# ChargeModule.net
KiCad netlist of a schematic drawn in EAGLE
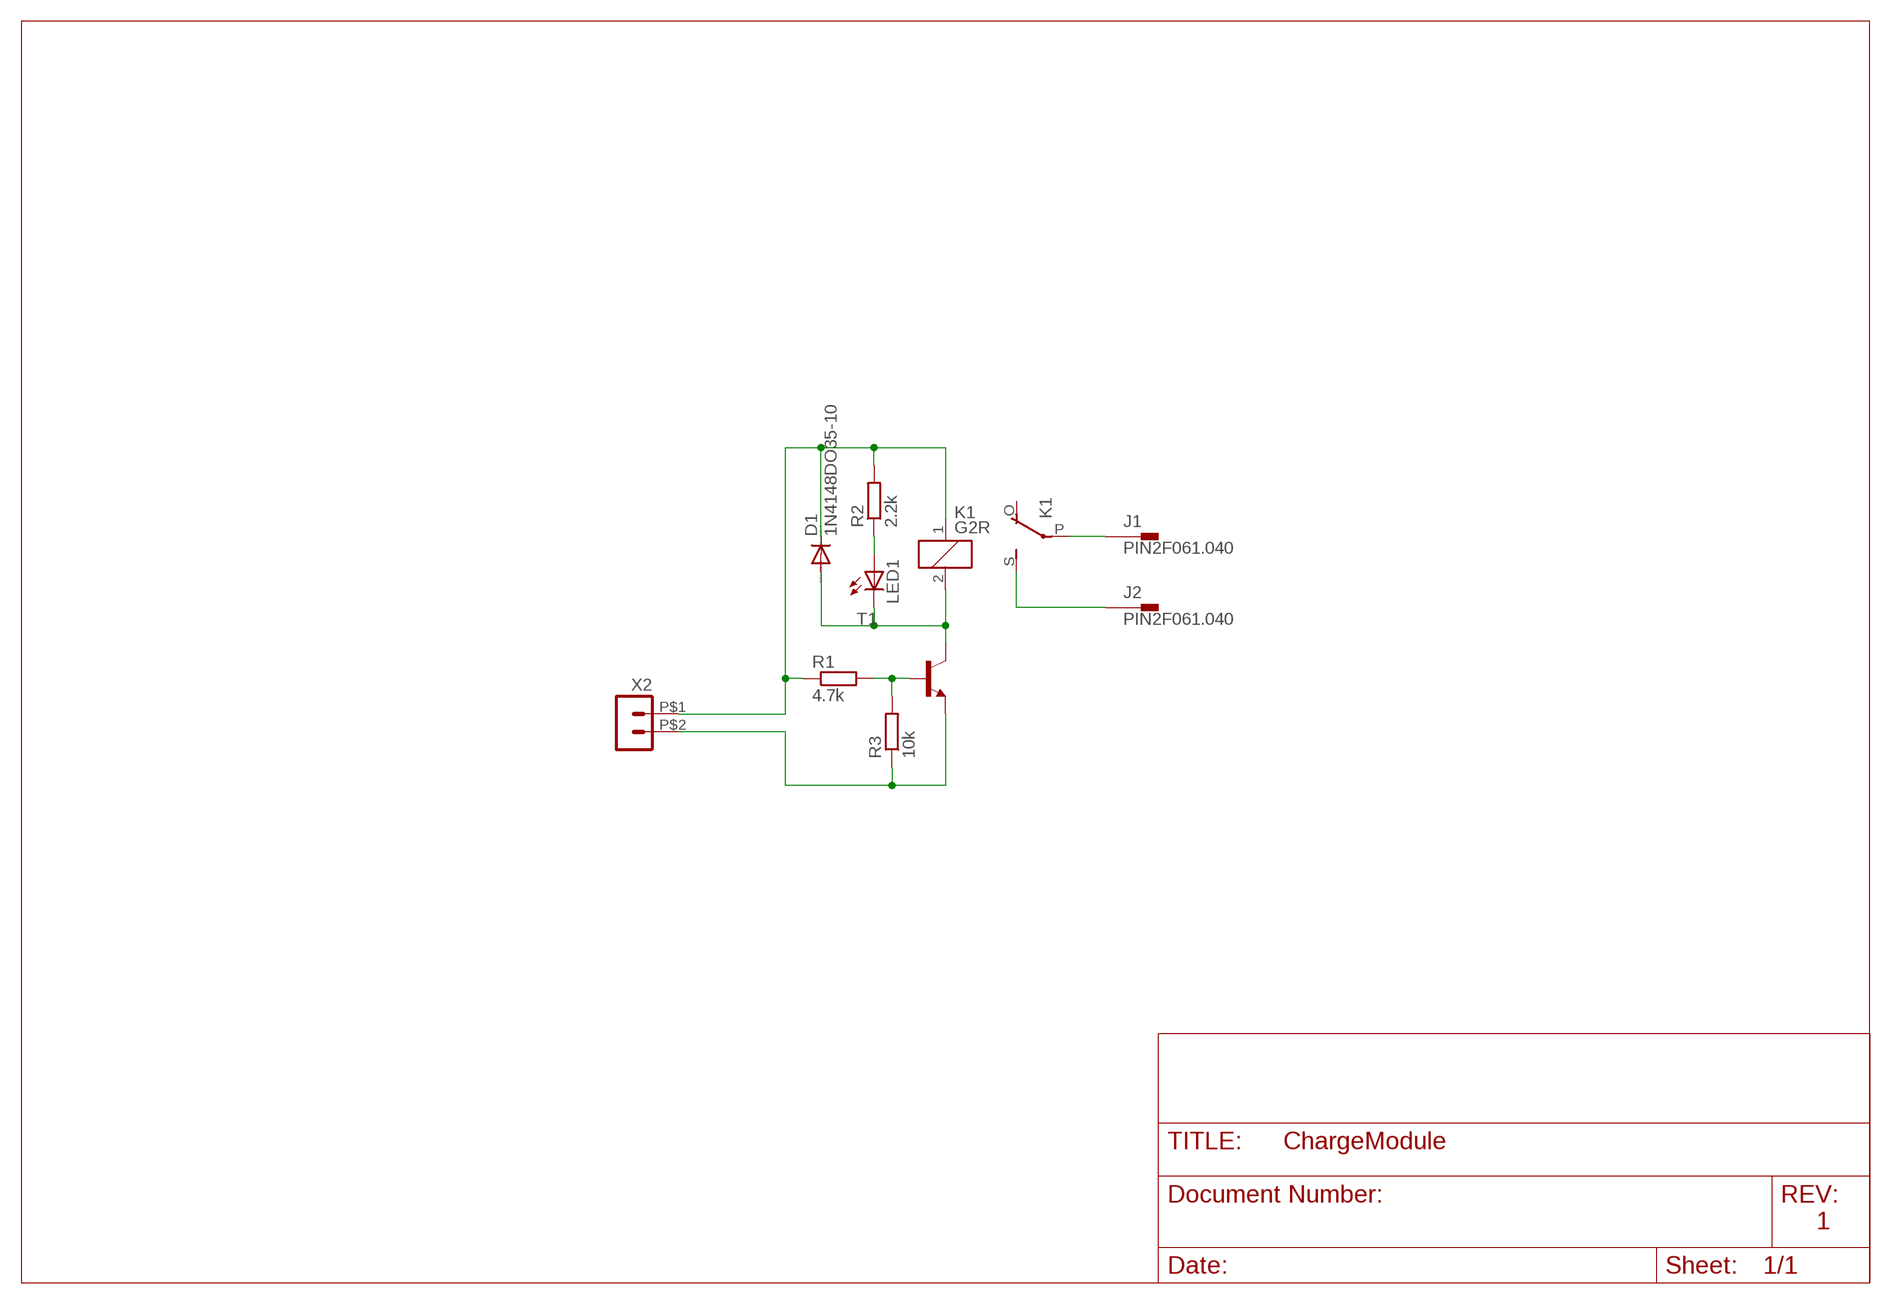
[diagram p0: schematic, sheet 1]

(export (version "E")
  (design (tool "Eeschema 10.0.6"))
  (components
    (comp (ref "D1")
      (value "1N4148DO35-10")
      (footprint "eagle-import:DO35-10")
      (libsource (lib "eagle-import") (part "1N4148DO35-10"))
    )
    (comp (ref "J1")
      (value "PIN2F061.040")
      (footprint "eagle-import:F061.040")
      (libsource (lib "eagle-import") (part "PIN2F061.040"))
    )
    (comp (ref "J2")
      (value "PIN2F061.040")
      (footprint "eagle-import:F061.040")
      (libsource (lib "eagle-import") (part "PIN2F061.040"))
    )
    (comp (ref "K1")
      (value "G2R")
      (footprint "eagle-import:G2R")
      (libsource (lib "eagle-import") (part "G2R"))
    )
    (comp (ref "LED1")
      (value "LED3MM")
      (footprint "eagle-import:LED3MM")
      (libsource (lib "eagle-import") (part "LED3MM"))
    )
    (comp (ref "R1")
      (value "4.7k")
      (footprint "eagle-import:0207_10")
      (libsource (lib "eagle-import") (part "R-EU_0207/10"))
    )
    (comp (ref "R2")
      (value "2.2k")
      (footprint "eagle-import:0207_10")
      (libsource (lib "eagle-import") (part "R-EU_0207/10"))
    )
    (comp (ref "R3")
      (value "10k")
      (footprint "eagle-import:0207_10")
      (libsource (lib "eagle-import") (part "R-EU_0207/10"))
    )
    (comp (ref "T1")
      (value "BC337-16-NPN-TO92-CBE")
      (footprint "eagle-import:TO92-CBE")
      (libsource (lib "eagle-import") (part "-NPN-TO92-CBEBC337-16"))
    )
    (comp (ref "X2")
      (value "HEADER_POS2_43650-0200")
      (footprint "eagle-import:43650-0200")
      (libsource (lib "eagle-import") (part "HEADER_POS2_?43650-0200"))
    )
  )
  (nets
    (net (code "1") (name "Net-(J1-1-PadA1)") (class "Default")
      (node (ref "J1") (pin "A1") (pinfunction "1_A1") (pintype "passive"))
      (node (ref "J1") (pin "A2") (pinfunction "1_A2") (pintype "passive"))
      (node (ref "K1") (pin "P") (pinfunction "P_P") (pintype "passive"))
    )
    (net (code "2") (name "Net-(J2-1-PadA1)") (class "Default")
      (node (ref "J2") (pin "A1") (pinfunction "1_A1") (pintype "passive"))
      (node (ref "J2") (pin "A2") (pinfunction "1_A2") (pintype "passive"))
      (node (ref "K1") (pin "S") (pinfunction "S_S") (pintype "passive"))
    )
    (net (code "3") (name "Net-(LED1-C)") (class "Default")
      (node (ref "D1") (pin "A") (pinfunction "A_A") (pintype "passive"))
      (node (ref "K1") (pin "2") (pinfunction "2_2") (pintype "passive"))
      (node (ref "LED1") (pin "K") (pinfunction "C_K") (pintype "passive"))
      (node (ref "T1") (pin "C") (pinfunction "C_C") (pintype "passive"))
    )
    (net (code "4") (name "Net-(LED1-PadA)") (class "Default")
      (node (ref "LED1") (pin "A") (pinfunction "A_A") (pintype "passive"))
      (node (ref "R2") (pin "1") (pinfunction "1_1") (pintype "passive"))
    )
    (net (code "5") (name "Net-(R1-Pad2)") (class "Default")
      (node (ref "R1") (pin "2") (pinfunction "2_2") (pintype "passive"))
      (node (ref "R3") (pin "2") (pinfunction "2_2") (pintype "passive"))
      (node (ref "T1") (pin "B") (pinfunction "B_B") (pintype "passive"))
    )
    (net (code "6") (name "Net-(X2-1)") (class "Default")
      (node (ref "D1") (pin "C") (pinfunction "C_C") (pintype "passive"))
      (node (ref "K1") (pin "1") (pinfunction "1_1") (pintype "passive"))
      (node (ref "R1") (pin "1") (pinfunction "1_1") (pintype "passive"))
      (node (ref "R2") (pin "2") (pinfunction "2_2") (pintype "passive"))
      (node (ref "X2") (pin "P$1") (pinfunction "1_P$1") (pintype "passive"))
    )
    (net (code "7") (name "Net-(X2-2)") (class "Default")
      (node (ref "R3") (pin "1") (pinfunction "1_1") (pintype "passive"))
      (node (ref "T1") (pin "E") (pinfunction "E_E") (pintype "passive"))
      (node (ref "X2") (pin "P$2") (pinfunction "2_P$2") (pintype "passive"))
    )
    (net (code "8") (name "unconnected-(K1-PadO)") (class "Default")
      (node (ref "K1") (pin "O") (pinfunction "O_O") (pintype "passive"))
    )
  )
)
